# mainboard.net
KiCad netlist of a schematic drawn in EAGLE
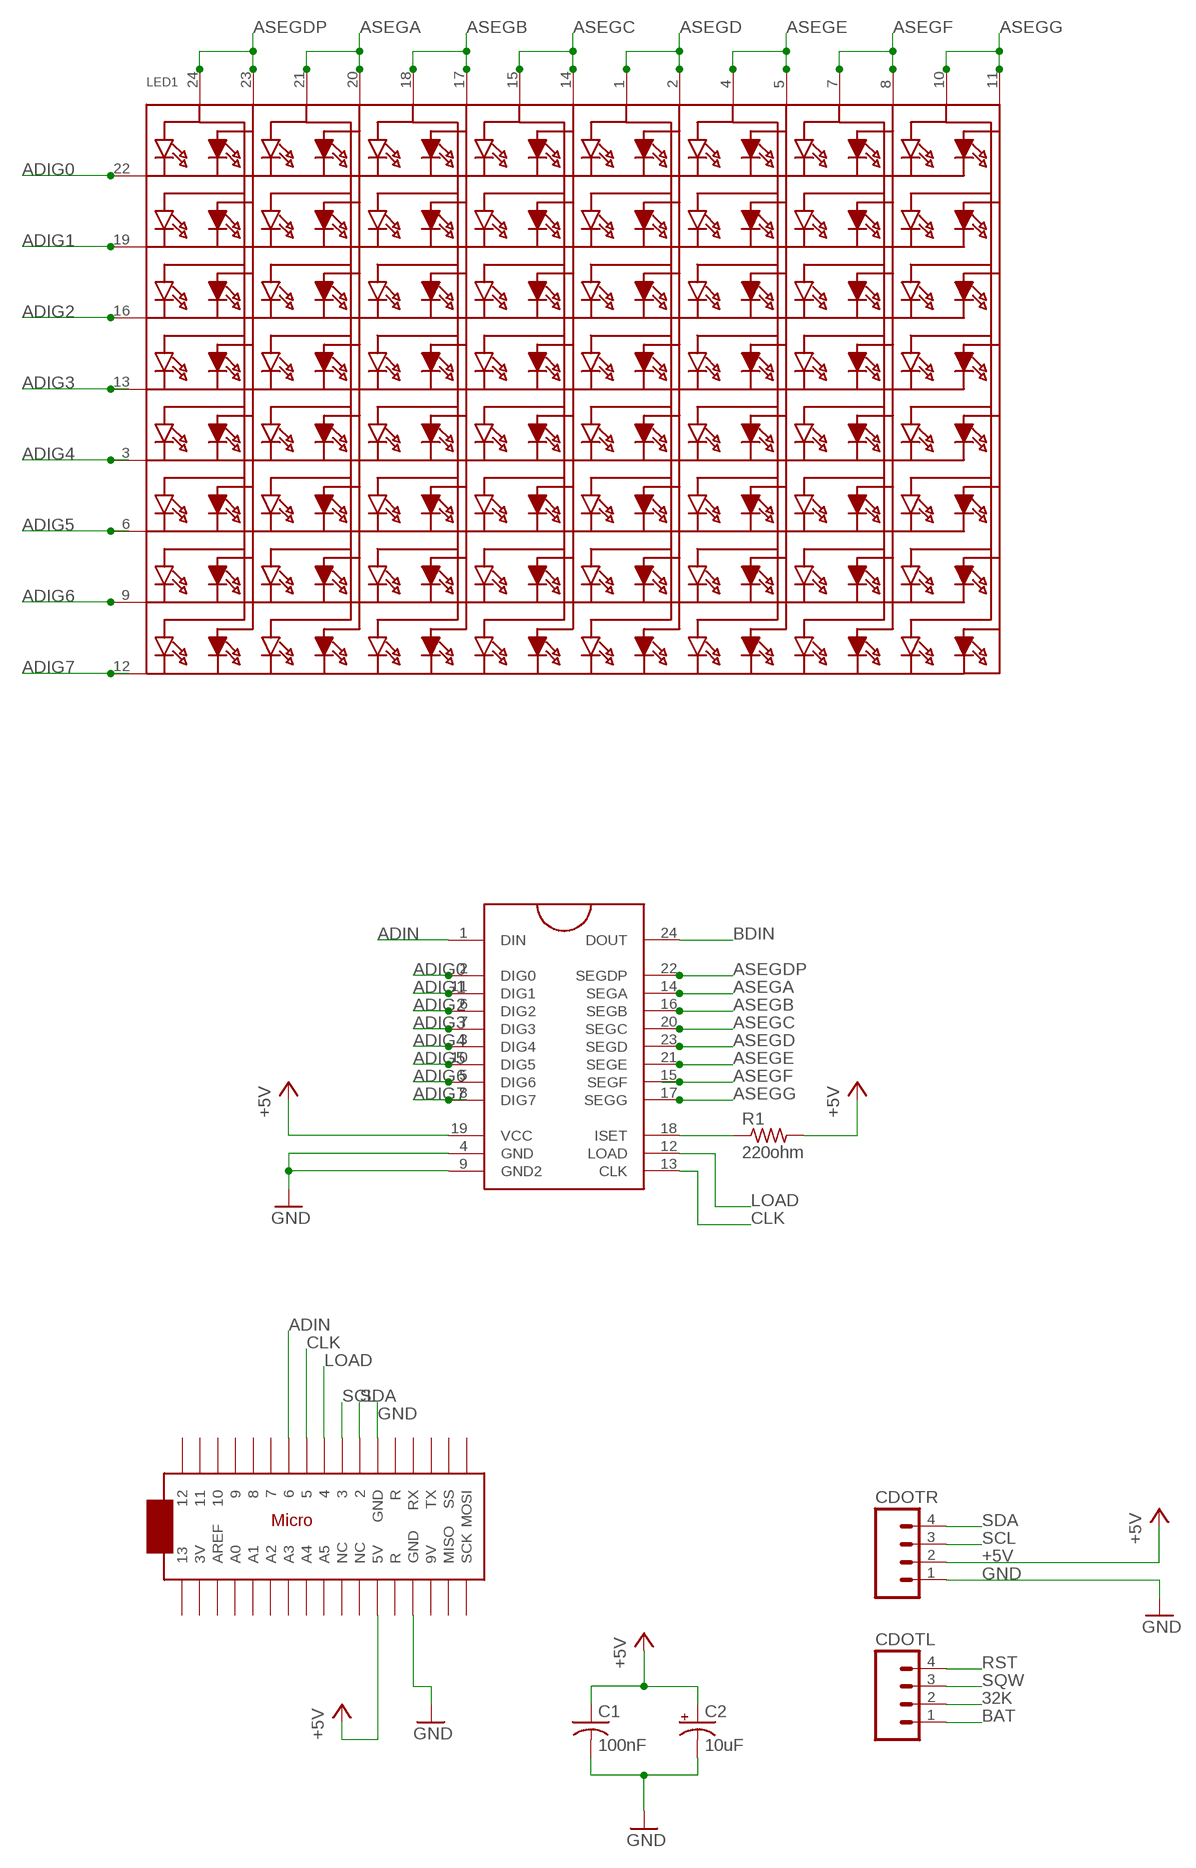
[diagram p0: schematic, sheet 1, part 1 of 2]
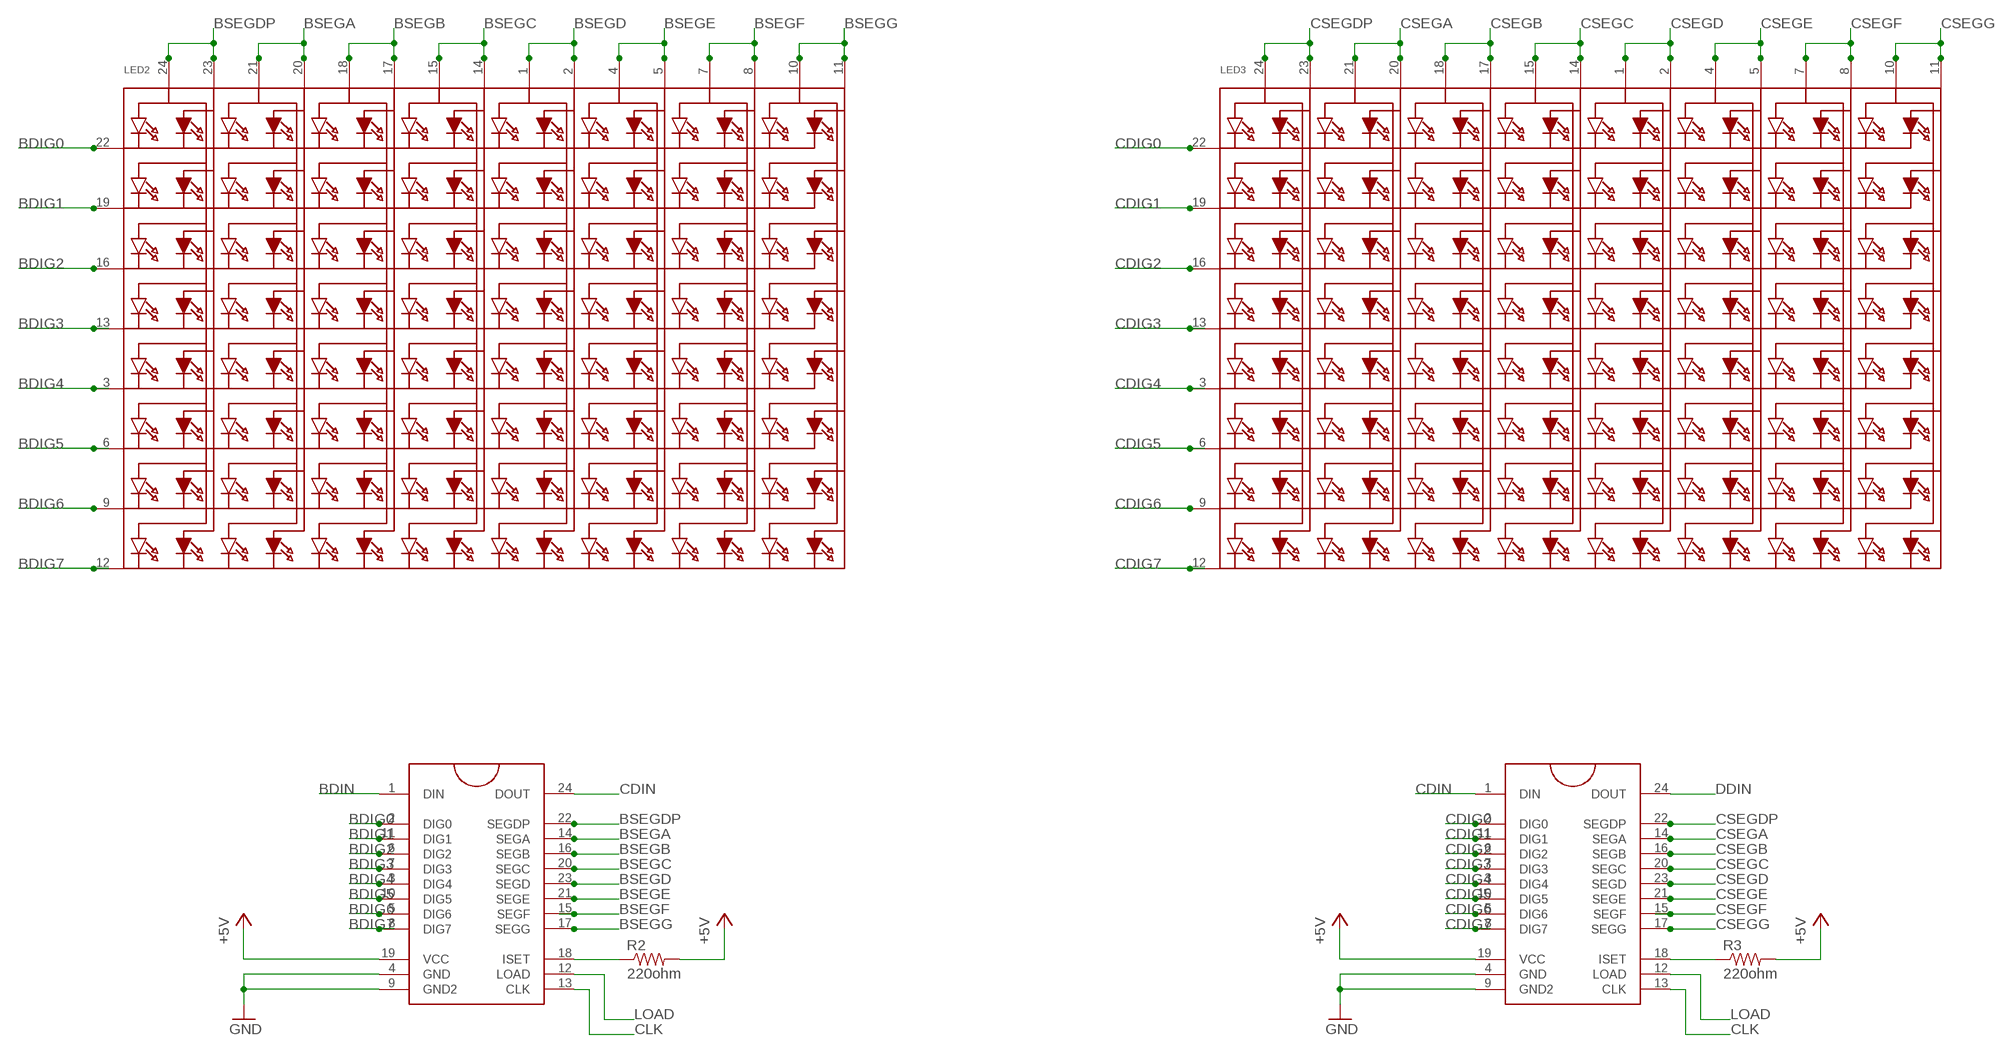
[diagram p1: schematic, sheet 1, part 2 of 2]

(export (version "E")
  (design (tool "Eeschema 10.0.6"))
  (components
    (comp (ref "ARDUINO")
      (value "ARDUINOMICRO")
      (footprint "eagle-import:ARDUINOMICRO")
      (libsource (lib "eagle-import") (part "ARDUINOMICRO"))
    )
    (comp (ref "C1")
      (value "100nF")
      (footprint "eagle-import:C050-030X075")
      (libsource (lib "eagle-import") (part "C-US050-030X075"))
    )
    (comp (ref "C2")
      (value "10uF")
      (footprint "eagle-import:E2,5-6")
      (libsource (lib "eagle-import") (part "CPOL-USE2.5-6"))
    )
    (comp (ref "CDOTL")
      (value "M04PTH")
      (footprint "eagle-import:1X04")
      (libsource (lib "eagle-import") (part "M04PTH"))
    )
    (comp (ref "CDOTR")
      (value "M04PTH")
      (footprint "eagle-import:1X04")
      (libsource (lib "eagle-import") (part "M04PTH"))
    )
    (comp (ref "LED1")
      (value "SEGMENT_8X8_BICOLOR_ROWCATHODEMI2A883XX")
      (footprint "eagle-import:SEGMENT_BICOL_BL-M12A883XX")
      (libsource (lib "eagle-import") (part "SEGMENT_8X8_BICOLOR_ROWCATHODEMI2A883XX"))
    )
    (comp (ref "LED2")
      (value "SEGMENT_8X8_BICOLOR_ROWCATHODEMI2A883XX")
      (footprint "eagle-import:SEGMENT_BICOL_BL-M12A883XX")
      (libsource (lib "eagle-import") (part "SEGMENT_8X8_BICOLOR_ROWCATHODEMI2A883XX"))
    )
    (comp (ref "LED3")
      (value "SEGMENT_8X8_BICOLOR_ROWCATHODEMI2A883XX")
      (footprint "eagle-import:SEGMENT_BICOL_BL-M12A883XX")
      (libsource (lib "eagle-import") (part "SEGMENT_8X8_BICOLOR_ROWCATHODEMI2A883XX"))
    )
    (comp (ref "MAX1")
      (value "MAX7219DIP")
      (footprint "eagle-import:DIL24")
      (libsource (lib "eagle-import") (part "MAX7219DIP"))
    )
    (comp (ref "MAX2")
      (value "MAX7219DIP")
      (footprint "eagle-import:DIL24")
      (libsource (lib "eagle-import") (part "MAX7219DIP"))
    )
    (comp (ref "MAX3")
      (value "MAX7219DIP")
      (footprint "eagle-import:DIL24")
      (libsource (lib "eagle-import") (part "MAX7219DIP"))
    )
    (comp (ref "R1")
      (value "220ohm")
      (footprint "eagle-import:0207_10")
      (libsource (lib "eagle-import") (part "R-US_0207/10"))
    )
    (comp (ref "R2")
      (value "220ohm")
      (footprint "eagle-import:0207_10")
      (libsource (lib "eagle-import") (part "R-US_0207/10"))
    )
    (comp (ref "R3")
      (value "220ohm")
      (footprint "eagle-import:0207_10")
      (libsource (lib "eagle-import") (part "R-US_0207/10"))
    )
  )
  (nets
    (net (code "1") (name "+5V") (class "Default")
      (node (ref "ARDUINO") (pin "P$23") (pinfunction "5V_P$23") (pintype "bidirectional"))
      (node (ref "C1") (pin "1") (pinfunction "1_1") (pintype "passive"))
      (node (ref "C2") (pin "+") (pinfunction "+_+") (pintype "passive"))
      (node (ref "CDOTR") (pin "2") (pinfunction "2_2") (pintype "passive"))
      (node (ref "MAX1") (pin "19") (pinfunction "VCC_19") (pintype "bidirectional"))
      (node (ref "MAX2") (pin "19") (pinfunction "VCC_19") (pintype "bidirectional"))
      (node (ref "MAX3") (pin "19") (pinfunction "VCC_19") (pintype "bidirectional"))
      (node (ref "R1") (pin "2") (pinfunction "2_2") (pintype "passive"))
      (node (ref "R2") (pin "2") (pinfunction "2_2") (pintype "passive"))
      (node (ref "R3") (pin "2") (pinfunction "2_2") (pintype "passive"))
    )
    (net (code "2") (name "/32K") (class "Default")
      (node (ref "CDOTL") (pin "2") (pinfunction "2_2") (pintype "passive"))
    )
    (net (code "3") (name "/ADIG0") (class "Default")
      (node (ref "LED1") (pin "22") (pinfunction "K1_22") (pintype "bidirectional"))
      (node (ref "MAX1") (pin "2") (pinfunction "DIG0_2") (pintype "bidirectional"))
    )
    (net (code "4") (name "/ADIG1") (class "Default")
      (node (ref "LED1") (pin "19") (pinfunction "K2_19") (pintype "bidirectional"))
      (node (ref "MAX1") (pin "11") (pinfunction "DIG1_11") (pintype "bidirectional"))
    )
    (net (code "5") (name "/ADIG2") (class "Default")
      (node (ref "LED1") (pin "16") (pinfunction "K3_16") (pintype "bidirectional"))
      (node (ref "MAX1") (pin "6") (pinfunction "DIG2_6") (pintype "bidirectional"))
    )
    (net (code "6") (name "/ADIG3") (class "Default")
      (node (ref "LED1") (pin "13") (pinfunction "K4_13") (pintype "bidirectional"))
      (node (ref "MAX1") (pin "7") (pinfunction "DIG3_7") (pintype "bidirectional"))
    )
    (net (code "7") (name "/ADIG4") (class "Default")
      (node (ref "LED1") (pin "3") (pinfunction "K5_3") (pintype "bidirectional"))
      (node (ref "MAX1") (pin "3") (pinfunction "DIG4_3") (pintype "bidirectional"))
    )
    (net (code "8") (name "/ADIG5") (class "Default")
      (node (ref "LED1") (pin "6") (pinfunction "K6_6") (pintype "bidirectional"))
      (node (ref "MAX1") (pin "10") (pinfunction "DIG5_10") (pintype "bidirectional"))
    )
    (net (code "9") (name "/ADIG6") (class "Default")
      (node (ref "LED1") (pin "9") (pinfunction "K7_9") (pintype "bidirectional"))
      (node (ref "MAX1") (pin "5") (pinfunction "DIG6_5") (pintype "bidirectional"))
    )
    (net (code "10") (name "/ADIG7") (class "Default")
      (node (ref "LED1") (pin "12") (pinfunction "K8_12") (pintype "bidirectional"))
      (node (ref "MAX1") (pin "8") (pinfunction "DIG7_8") (pintype "bidirectional"))
    )
    (net (code "11") (name "/ADIN") (class "Default")
      (node (ref "ARDUINO") (pin "P$7") (pinfunction "6_P$7") (pintype "bidirectional"))
      (node (ref "MAX1") (pin "1") (pinfunction "DIN_1") (pintype "bidirectional"))
    )
    (net (code "12") (name "/ASEGA") (class "Default")
      (node (ref "LED1") (pin "20") (pinfunction "A4_20") (pintype "bidirectional"))
      (node (ref "LED1") (pin "21") (pinfunction "A3_21") (pintype "bidirectional"))
      (node (ref "MAX1") (pin "14") (pinfunction "SEGA_14") (pintype "bidirectional"))
    )
    (net (code "13") (name "/ASEGB") (class "Default")
      (node (ref "LED1") (pin "17") (pinfunction "A6_17") (pintype "bidirectional"))
      (node (ref "LED1") (pin "18") (pinfunction "A5_18") (pintype "bidirectional"))
      (node (ref "MAX1") (pin "16") (pinfunction "SEGB_16") (pintype "bidirectional"))
    )
    (net (code "14") (name "/ASEGC") (class "Default")
      (node (ref "LED1") (pin "14") (pinfunction "A8_14") (pintype "bidirectional"))
      (node (ref "LED1") (pin "15") (pinfunction "A7_15") (pintype "bidirectional"))
      (node (ref "MAX1") (pin "20") (pinfunction "SEGC_20") (pintype "bidirectional"))
    )
    (net (code "15") (name "/ASEGD") (class "Default")
      (node (ref "LED1") (pin "1") (pinfunction "A9_1") (pintype "bidirectional"))
      (node (ref "LED1") (pin "2") (pinfunction "A10_2") (pintype "bidirectional"))
      (node (ref "MAX1") (pin "23") (pinfunction "SEGD_23") (pintype "bidirectional"))
    )
    (net (code "16") (name "/ASEGDP") (class "Default")
      (node (ref "LED1") (pin "23") (pinfunction "A2_23") (pintype "bidirectional"))
      (node (ref "LED1") (pin "24") (pinfunction "A1_24") (pintype "bidirectional"))
      (node (ref "MAX1") (pin "22") (pinfunction "SEGDP_22") (pintype "bidirectional"))
    )
    (net (code "17") (name "/ASEGE") (class "Default")
      (node (ref "LED1") (pin "4") (pinfunction "A11_4") (pintype "bidirectional"))
      (node (ref "LED1") (pin "5") (pinfunction "A12_5") (pintype "bidirectional"))
      (node (ref "MAX1") (pin "21") (pinfunction "SEGE_21") (pintype "bidirectional"))
    )
    (net (code "18") (name "/ASEGF") (class "Default")
      (node (ref "LED1") (pin "7") (pinfunction "A13_7") (pintype "bidirectional"))
      (node (ref "LED1") (pin "8") (pinfunction "A14_8") (pintype "bidirectional"))
      (node (ref "MAX1") (pin "15") (pinfunction "SEGF_15") (pintype "bidirectional"))
    )
    (net (code "19") (name "/ASEGG") (class "Default")
      (node (ref "LED1") (pin "10") (pinfunction "A15_10") (pintype "bidirectional"))
      (node (ref "LED1") (pin "11") (pinfunction "A16_11") (pintype "bidirectional"))
      (node (ref "MAX1") (pin "17") (pinfunction "SEGG_17") (pintype "bidirectional"))
    )
    (net (code "20") (name "/BAT") (class "Default")
      (node (ref "CDOTL") (pin "1") (pinfunction "1_1") (pintype "passive"))
    )
    (net (code "21") (name "/BDIG0") (class "Default")
      (node (ref "LED2") (pin "22") (pinfunction "K1_22") (pintype "bidirectional"))
      (node (ref "MAX2") (pin "2") (pinfunction "DIG0_2") (pintype "bidirectional"))
    )
    (net (code "22") (name "/BDIG1") (class "Default")
      (node (ref "LED2") (pin "19") (pinfunction "K2_19") (pintype "bidirectional"))
      (node (ref "MAX2") (pin "11") (pinfunction "DIG1_11") (pintype "bidirectional"))
    )
    (net (code "23") (name "/BDIG2") (class "Default")
      (node (ref "LED2") (pin "16") (pinfunction "K3_16") (pintype "bidirectional"))
      (node (ref "MAX2") (pin "6") (pinfunction "DIG2_6") (pintype "bidirectional"))
    )
    (net (code "24") (name "/BDIG3") (class "Default")
      (node (ref "LED2") (pin "13") (pinfunction "K4_13") (pintype "bidirectional"))
      (node (ref "MAX2") (pin "7") (pinfunction "DIG3_7") (pintype "bidirectional"))
    )
    (net (code "25") (name "/BDIG4") (class "Default")
      (node (ref "LED2") (pin "3") (pinfunction "K5_3") (pintype "bidirectional"))
      (node (ref "MAX2") (pin "3") (pinfunction "DIG4_3") (pintype "bidirectional"))
    )
    (net (code "26") (name "/BDIG5") (class "Default")
      (node (ref "LED2") (pin "6") (pinfunction "K6_6") (pintype "bidirectional"))
      (node (ref "MAX2") (pin "10") (pinfunction "DIG5_10") (pintype "bidirectional"))
    )
    (net (code "27") (name "/BDIG6") (class "Default")
      (node (ref "LED2") (pin "9") (pinfunction "K7_9") (pintype "bidirectional"))
      (node (ref "MAX2") (pin "5") (pinfunction "DIG6_5") (pintype "bidirectional"))
    )
    (net (code "28") (name "/BDIG7") (class "Default")
      (node (ref "LED2") (pin "12") (pinfunction "K8_12") (pintype "bidirectional"))
      (node (ref "MAX2") (pin "8") (pinfunction "DIG7_8") (pintype "bidirectional"))
    )
    (net (code "29") (name "/BDIN") (class "Default")
      (node (ref "MAX1") (pin "24") (pinfunction "DOUT_24") (pintype "bidirectional"))
      (node (ref "MAX2") (pin "1") (pinfunction "DIN_1") (pintype "bidirectional"))
    )
    (net (code "30") (name "/BSEGA") (class "Default")
      (node (ref "LED2") (pin "20") (pinfunction "A4_20") (pintype "bidirectional"))
      (node (ref "LED2") (pin "21") (pinfunction "A3_21") (pintype "bidirectional"))
      (node (ref "MAX2") (pin "14") (pinfunction "SEGA_14") (pintype "bidirectional"))
    )
    (net (code "31") (name "/BSEGB") (class "Default")
      (node (ref "LED2") (pin "17") (pinfunction "A6_17") (pintype "bidirectional"))
      (node (ref "LED2") (pin "18") (pinfunction "A5_18") (pintype "bidirectional"))
      (node (ref "MAX2") (pin "16") (pinfunction "SEGB_16") (pintype "bidirectional"))
    )
    (net (code "32") (name "/BSEGC") (class "Default")
      (node (ref "LED2") (pin "14") (pinfunction "A8_14") (pintype "bidirectional"))
      (node (ref "LED2") (pin "15") (pinfunction "A7_15") (pintype "bidirectional"))
      (node (ref "MAX2") (pin "20") (pinfunction "SEGC_20") (pintype "bidirectional"))
    )
    (net (code "33") (name "/BSEGD") (class "Default")
      (node (ref "LED2") (pin "1") (pinfunction "A9_1") (pintype "bidirectional"))
      (node (ref "LED2") (pin "2") (pinfunction "A10_2") (pintype "bidirectional"))
      (node (ref "MAX2") (pin "23") (pinfunction "SEGD_23") (pintype "bidirectional"))
    )
    (net (code "34") (name "/BSEGDP") (class "Default")
      (node (ref "LED2") (pin "23") (pinfunction "A2_23") (pintype "bidirectional"))
      (node (ref "LED2") (pin "24") (pinfunction "A1_24") (pintype "bidirectional"))
      (node (ref "MAX2") (pin "22") (pinfunction "SEGDP_22") (pintype "bidirectional"))
    )
    (net (code "35") (name "/BSEGE") (class "Default")
      (node (ref "LED2") (pin "4") (pinfunction "A11_4") (pintype "bidirectional"))
      (node (ref "LED2") (pin "5") (pinfunction "A12_5") (pintype "bidirectional"))
      (node (ref "MAX2") (pin "21") (pinfunction "SEGE_21") (pintype "bidirectional"))
    )
    (net (code "36") (name "/BSEGF") (class "Default")
      (node (ref "LED2") (pin "7") (pinfunction "A13_7") (pintype "bidirectional"))
      (node (ref "LED2") (pin "8") (pinfunction "A14_8") (pintype "bidirectional"))
      (node (ref "MAX2") (pin "15") (pinfunction "SEGF_15") (pintype "bidirectional"))
    )
    (net (code "37") (name "/BSEGG") (class "Default")
      (node (ref "LED2") (pin "10") (pinfunction "A15_10") (pintype "bidirectional"))
      (node (ref "LED2") (pin "11") (pinfunction "A16_11") (pintype "bidirectional"))
      (node (ref "MAX2") (pin "17") (pinfunction "SEGG_17") (pintype "bidirectional"))
    )
    (net (code "38") (name "/CDIG0") (class "Default")
      (node (ref "LED3") (pin "22") (pinfunction "K1_22") (pintype "bidirectional"))
      (node (ref "MAX3") (pin "2") (pinfunction "DIG0_2") (pintype "bidirectional"))
    )
    (net (code "39") (name "/CDIG1") (class "Default")
      (node (ref "LED3") (pin "19") (pinfunction "K2_19") (pintype "bidirectional"))
      (node (ref "MAX3") (pin "11") (pinfunction "DIG1_11") (pintype "bidirectional"))
    )
    (net (code "40") (name "/CDIG2") (class "Default")
      (node (ref "LED3") (pin "16") (pinfunction "K3_16") (pintype "bidirectional"))
      (node (ref "MAX3") (pin "6") (pinfunction "DIG2_6") (pintype "bidirectional"))
    )
    (net (code "41") (name "/CDIG3") (class "Default")
      (node (ref "LED3") (pin "13") (pinfunction "K4_13") (pintype "bidirectional"))
      (node (ref "MAX3") (pin "7") (pinfunction "DIG3_7") (pintype "bidirectional"))
    )
    (net (code "42") (name "/CDIG4") (class "Default")
      (node (ref "LED3") (pin "3") (pinfunction "K5_3") (pintype "bidirectional"))
      (node (ref "MAX3") (pin "3") (pinfunction "DIG4_3") (pintype "bidirectional"))
    )
    (net (code "43") (name "/CDIG5") (class "Default")
      (node (ref "LED3") (pin "6") (pinfunction "K6_6") (pintype "bidirectional"))
      (node (ref "MAX3") (pin "10") (pinfunction "DIG5_10") (pintype "bidirectional"))
    )
    (net (code "44") (name "/CDIG6") (class "Default")
      (node (ref "LED3") (pin "9") (pinfunction "K7_9") (pintype "bidirectional"))
      (node (ref "MAX3") (pin "5") (pinfunction "DIG6_5") (pintype "bidirectional"))
    )
    (net (code "45") (name "/CDIG7") (class "Default")
      (node (ref "LED3") (pin "12") (pinfunction "K8_12") (pintype "bidirectional"))
      (node (ref "MAX3") (pin "8") (pinfunction "DIG7_8") (pintype "bidirectional"))
    )
    (net (code "46") (name "/CDIN") (class "Default")
      (node (ref "MAX2") (pin "24") (pinfunction "DOUT_24") (pintype "bidirectional"))
      (node (ref "MAX3") (pin "1") (pinfunction "DIN_1") (pintype "bidirectional"))
    )
    (net (code "47") (name "/CLK") (class "Default")
      (node (ref "ARDUINO") (pin "P$8") (pinfunction "5_P$8") (pintype "bidirectional"))
      (node (ref "MAX1") (pin "13") (pinfunction "CLK_13") (pintype "bidirectional"))
      (node (ref "MAX2") (pin "13") (pinfunction "CLK_13") (pintype "bidirectional"))
      (node (ref "MAX3") (pin "13") (pinfunction "CLK_13") (pintype "bidirectional"))
    )
    (net (code "48") (name "/CSEGA") (class "Default")
      (node (ref "LED3") (pin "20") (pinfunction "A4_20") (pintype "bidirectional"))
      (node (ref "LED3") (pin "21") (pinfunction "A3_21") (pintype "bidirectional"))
      (node (ref "MAX3") (pin "14") (pinfunction "SEGA_14") (pintype "bidirectional"))
    )
    (net (code "49") (name "/CSEGB") (class "Default")
      (node (ref "LED3") (pin "17") (pinfunction "A6_17") (pintype "bidirectional"))
      (node (ref "LED3") (pin "18") (pinfunction "A5_18") (pintype "bidirectional"))
      (node (ref "MAX3") (pin "16") (pinfunction "SEGB_16") (pintype "bidirectional"))
    )
    (net (code "50") (name "/CSEGC") (class "Default")
      (node (ref "LED3") (pin "14") (pinfunction "A8_14") (pintype "bidirectional"))
      (node (ref "LED3") (pin "15") (pinfunction "A7_15") (pintype "bidirectional"))
      (node (ref "MAX3") (pin "20") (pinfunction "SEGC_20") (pintype "bidirectional"))
    )
    (net (code "51") (name "/CSEGD") (class "Default")
      (node (ref "LED3") (pin "1") (pinfunction "A9_1") (pintype "bidirectional"))
      (node (ref "LED3") (pin "2") (pinfunction "A10_2") (pintype "bidirectional"))
      (node (ref "MAX3") (pin "23") (pinfunction "SEGD_23") (pintype "bidirectional"))
    )
    (net (code "52") (name "/CSEGDP") (class "Default")
      (node (ref "LED3") (pin "23") (pinfunction "A2_23") (pintype "bidirectional"))
      (node (ref "LED3") (pin "24") (pinfunction "A1_24") (pintype "bidirectional"))
      (node (ref "MAX3") (pin "22") (pinfunction "SEGDP_22") (pintype "bidirectional"))
    )
    (net (code "53") (name "/CSEGE") (class "Default")
      (node (ref "LED3") (pin "4") (pinfunction "A11_4") (pintype "bidirectional"))
      (node (ref "LED3") (pin "5") (pinfunction "A12_5") (pintype "bidirectional"))
      (node (ref "MAX3") (pin "21") (pinfunction "SEGE_21") (pintype "bidirectional"))
    )
    (net (code "54") (name "/CSEGF") (class "Default")
      (node (ref "LED3") (pin "7") (pinfunction "A13_7") (pintype "bidirectional"))
      (node (ref "LED3") (pin "8") (pinfunction "A14_8") (pintype "bidirectional"))
      (node (ref "MAX3") (pin "15") (pinfunction "SEGF_15") (pintype "bidirectional"))
    )
    (net (code "55") (name "/CSEGG") (class "Default")
      (node (ref "LED3") (pin "10") (pinfunction "A15_10") (pintype "bidirectional"))
      (node (ref "LED3") (pin "11") (pinfunction "A16_11") (pintype "bidirectional"))
      (node (ref "MAX3") (pin "17") (pinfunction "SEGG_17") (pintype "bidirectional"))
    )
    (net (code "56") (name "/DDIN") (class "Default")
      (node (ref "MAX3") (pin "24") (pinfunction "DOUT_24") (pintype "bidirectional"))
    )
    (net (code "57") (name "/LOAD") (class "Default")
      (node (ref "ARDUINO") (pin "P$9") (pinfunction "4_P$9") (pintype "bidirectional"))
      (node (ref "MAX1") (pin "12") (pinfunction "LOAD_12") (pintype "bidirectional"))
      (node (ref "MAX2") (pin "12") (pinfunction "LOAD_12") (pintype "bidirectional"))
      (node (ref "MAX3") (pin "12") (pinfunction "LOAD_12") (pintype "bidirectional"))
    )
    (net (code "58") (name "/RST") (class "Default")
      (node (ref "CDOTL") (pin "4") (pinfunction "4_4") (pintype "passive"))
    )
    (net (code "59") (name "/SCL") (class "Default")
      (node (ref "ARDUINO") (pin "P$10") (pinfunction "3_P$10") (pintype "bidirectional"))
      (node (ref "CDOTR") (pin "3") (pinfunction "3_3") (pintype "passive"))
    )
    (net (code "60") (name "/SDA") (class "Default")
      (node (ref "ARDUINO") (pin "P$11") (pinfunction "2_P$11") (pintype "bidirectional"))
      (node (ref "CDOTR") (pin "4") (pinfunction "4_4") (pintype "passive"))
    )
    (net (code "61") (name "/SQW") (class "Default")
      (node (ref "CDOTL") (pin "3") (pinfunction "3_3") (pintype "passive"))
    )
    (net (code "62") (name "GND") (class "Default")
      (node (ref "ARDUINO") (pin "P$12") (pinfunction "GND_P$12") (pintype "bidirectional"))
      (node (ref "ARDUINO") (pin "P$21") (pinfunction "GND_P$21") (pintype "bidirectional"))
      (node (ref "C1") (pin "2") (pinfunction "2_2") (pintype "passive"))
      (node (ref "C2") (pin "-") (pinfunction "-_-") (pintype "passive"))
      (node (ref "CDOTR") (pin "1") (pinfunction "1_1") (pintype "passive"))
      (node (ref "MAX1") (pin "4") (pinfunction "GND_4") (pintype "bidirectional"))
      (node (ref "MAX1") (pin "9") (pinfunction "GND2_9") (pintype "bidirectional"))
      (node (ref "MAX2") (pin "4") (pinfunction "GND_4") (pintype "bidirectional"))
      (node (ref "MAX2") (pin "9") (pinfunction "GND2_9") (pintype "bidirectional"))
      (node (ref "MAX3") (pin "4") (pinfunction "GND_4") (pintype "bidirectional"))
      (node (ref "MAX3") (pin "9") (pinfunction "GND2_9") (pintype "bidirectional"))
    )
    (net (code "63") (name "Net-(MAX1-ISET)") (class "Default")
      (node (ref "MAX1") (pin "18") (pinfunction "ISET_18") (pintype "bidirectional"))
      (node (ref "R1") (pin "1") (pinfunction "1_1") (pintype "passive"))
    )
    (net (code "64") (name "Net-(MAX2-ISET)") (class "Default")
      (node (ref "MAX2") (pin "18") (pinfunction "ISET_18") (pintype "bidirectional"))
      (node (ref "R2") (pin "1") (pinfunction "1_1") (pintype "passive"))
    )
    (net (code "65") (name "Net-(MAX3-ISET)") (class "Default")
      (node (ref "MAX3") (pin "18") (pinfunction "ISET_18") (pintype "bidirectional"))
      (node (ref "R3") (pin "1") (pinfunction "1_1") (pintype "passive"))
    )
    (net (code "66") (name "unconnected-(ARDUINO-3V-PadP$33)") (class "Default")
      (node (ref "ARDUINO") (pin "P$33") (pinfunction "3V_P$33") (pintype "bidirectional"))
    )
    (net (code "67") (name "unconnected-(ARDUINO-7-PadP$6)") (class "Default")
      (node (ref "ARDUINO") (pin "P$6") (pinfunction "7_P$6") (pintype "bidirectional"))
    )
    (net (code "68") (name "unconnected-(ARDUINO-8-PadP$5)") (class "Default")
      (node (ref "ARDUINO") (pin "P$5") (pinfunction "8_P$5") (pintype "bidirectional"))
    )
    (net (code "69") (name "unconnected-(ARDUINO-9-PadP$4)") (class "Default")
      (node (ref "ARDUINO") (pin "P$4") (pinfunction "9_P$4") (pintype "bidirectional"))
    )
    (net (code "70") (name "unconnected-(ARDUINO-9V-PadP$20)") (class "Default")
      (node (ref "ARDUINO") (pin "P$20") (pinfunction "9V_P$20") (pintype "bidirectional"))
    )
    (net (code "71") (name "unconnected-(ARDUINO-10-PadP$3)") (class "Default")
      (node (ref "ARDUINO") (pin "P$3") (pinfunction "10_P$3") (pintype "bidirectional"))
    )
    (net (code "72") (name "unconnected-(ARDUINO-11-PadP$2)") (class "Default")
      (node (ref "ARDUINO") (pin "P$2") (pinfunction "11_P$2") (pintype "bidirectional"))
    )
    (net (code "73") (name "unconnected-(ARDUINO-12-PadP$1)") (class "Default")
      (node (ref "ARDUINO") (pin "P$1") (pinfunction "12_P$1") (pintype "bidirectional"))
    )
    (net (code "74") (name "unconnected-(ARDUINO-13-PadP$34)") (class "Default")
      (node (ref "ARDUINO") (pin "P$34") (pinfunction "13_P$34") (pintype "bidirectional"))
    )
    (net (code "75") (name "unconnected-(ARDUINO-A0-PadP$31)") (class "Default")
      (node (ref "ARDUINO") (pin "P$31") (pinfunction "A0_P$31") (pintype "bidirectional"))
    )
    (net (code "76") (name "unconnected-(ARDUINO-A1-PadP$30)") (class "Default")
      (node (ref "ARDUINO") (pin "P$30") (pinfunction "A1_P$30") (pintype "bidirectional"))
    )
    (net (code "77") (name "unconnected-(ARDUINO-A2-PadP$29)") (class "Default")
      (node (ref "ARDUINO") (pin "P$29") (pinfunction "A2_P$29") (pintype "bidirectional"))
    )
    (net (code "78") (name "unconnected-(ARDUINO-A3-PadP$28)") (class "Default")
      (node (ref "ARDUINO") (pin "P$28") (pinfunction "A3_P$28") (pintype "bidirectional"))
    )
    (net (code "79") (name "unconnected-(ARDUINO-A4-PadP$27)") (class "Default")
      (node (ref "ARDUINO") (pin "P$27") (pinfunction "A4_P$27") (pintype "bidirectional"))
    )
    (net (code "80") (name "unconnected-(ARDUINO-A5-PadP$26)") (class "Default")
      (node (ref "ARDUINO") (pin "P$26") (pinfunction "A5_P$26") (pintype "bidirectional"))
    )
    (net (code "81") (name "unconnected-(ARDUINO-AREF-PadP$32)") (class "Default")
      (node (ref "ARDUINO") (pin "P$32") (pinfunction "AREF_P$32") (pintype "bidirectional"))
    )
    (net (code "82") (name "unconnected-(ARDUINO-MISO-PadP$19)") (class "Default")
      (node (ref "ARDUINO") (pin "P$19") (pinfunction "MISO_P$19") (pintype "bidirectional"))
    )
    (net (code "83") (name "unconnected-(ARDUINO-MOSI-PadP$17)") (class "Default")
      (node (ref "ARDUINO") (pin "P$17") (pinfunction "MOSI_P$17") (pintype "bidirectional"))
    )
    (net (code "84") (name "unconnected-(ARDUINO-NC-PadP$24)") (class "Default")
      (node (ref "ARDUINO") (pin "P$24") (pinfunction "NC_P$24") (pintype "bidirectional"))
    )
    (net (code "85") (name "unconnected-(ARDUINO-NC-PadP$25)") (class "Default")
      (node (ref "ARDUINO") (pin "P$25") (pinfunction "NC_P$25") (pintype "bidirectional"))
    )
    (net (code "86") (name "unconnected-(ARDUINO-R-PadP$13)") (class "Default")
      (node (ref "ARDUINO") (pin "P$13") (pinfunction "R_P$13") (pintype "bidirectional"))
    )
    (net (code "87") (name "unconnected-(ARDUINO-R-PadP$22)") (class "Default")
      (node (ref "ARDUINO") (pin "P$22") (pinfunction "R_P$22") (pintype "bidirectional"))
    )
    (net (code "88") (name "unconnected-(ARDUINO-RX-PadP$14)") (class "Default")
      (node (ref "ARDUINO") (pin "P$14") (pinfunction "RX_P$14") (pintype "bidirectional"))
    )
    (net (code "89") (name "unconnected-(ARDUINO-SCK-PadP$18)") (class "Default")
      (node (ref "ARDUINO") (pin "P$18") (pinfunction "SCK_P$18") (pintype "bidirectional"))
    )
    (net (code "90") (name "unconnected-(ARDUINO-SS-PadP$16)") (class "Default")
      (node (ref "ARDUINO") (pin "P$16") (pinfunction "SS_P$16") (pintype "bidirectional"))
    )
    (net (code "91") (name "unconnected-(ARDUINO-TX-PadP$15)") (class "Default")
      (node (ref "ARDUINO") (pin "P$15") (pinfunction "TX_P$15") (pintype "bidirectional"))
    )
  )
)
